# camera_connector.net
KiCad netlist of a schematic drawn in Altium Designer
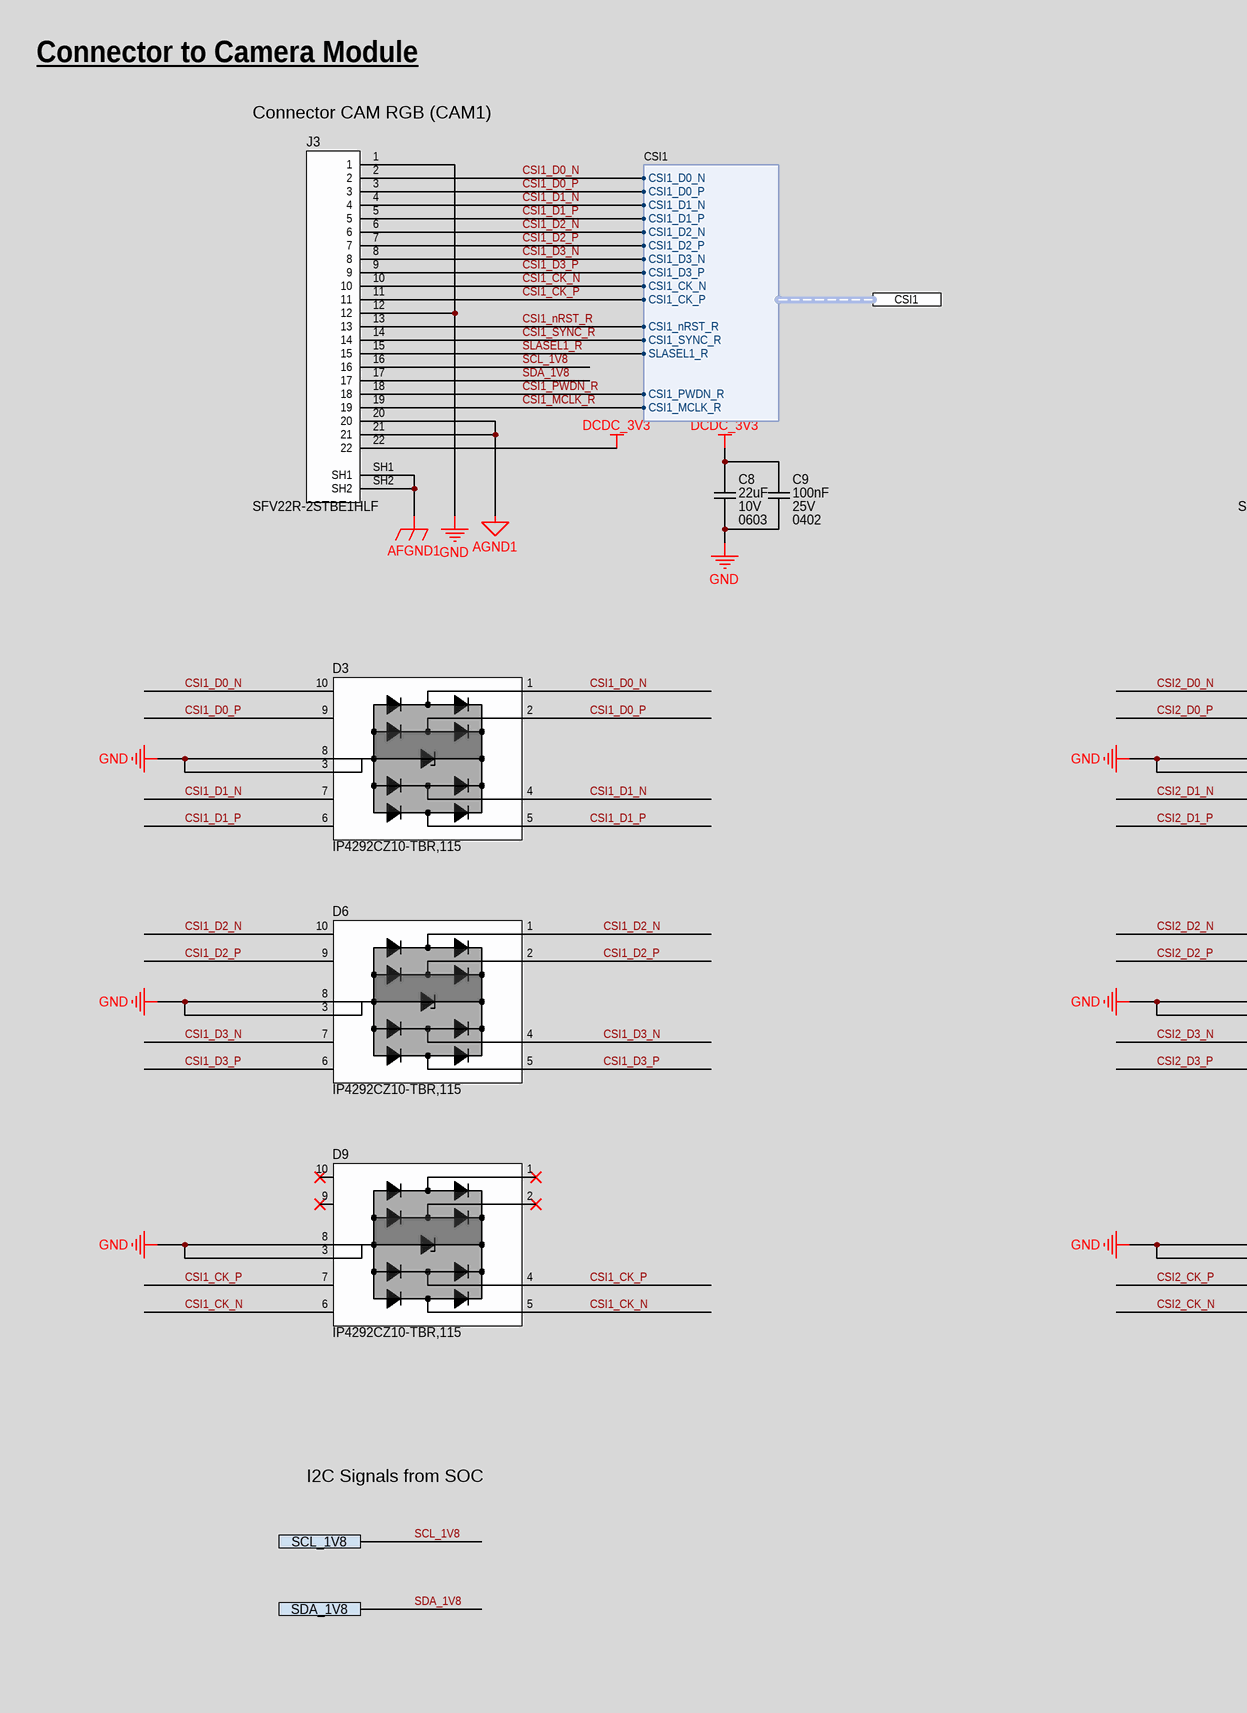
[diagram p0: camera_connector.SchDoc, left]
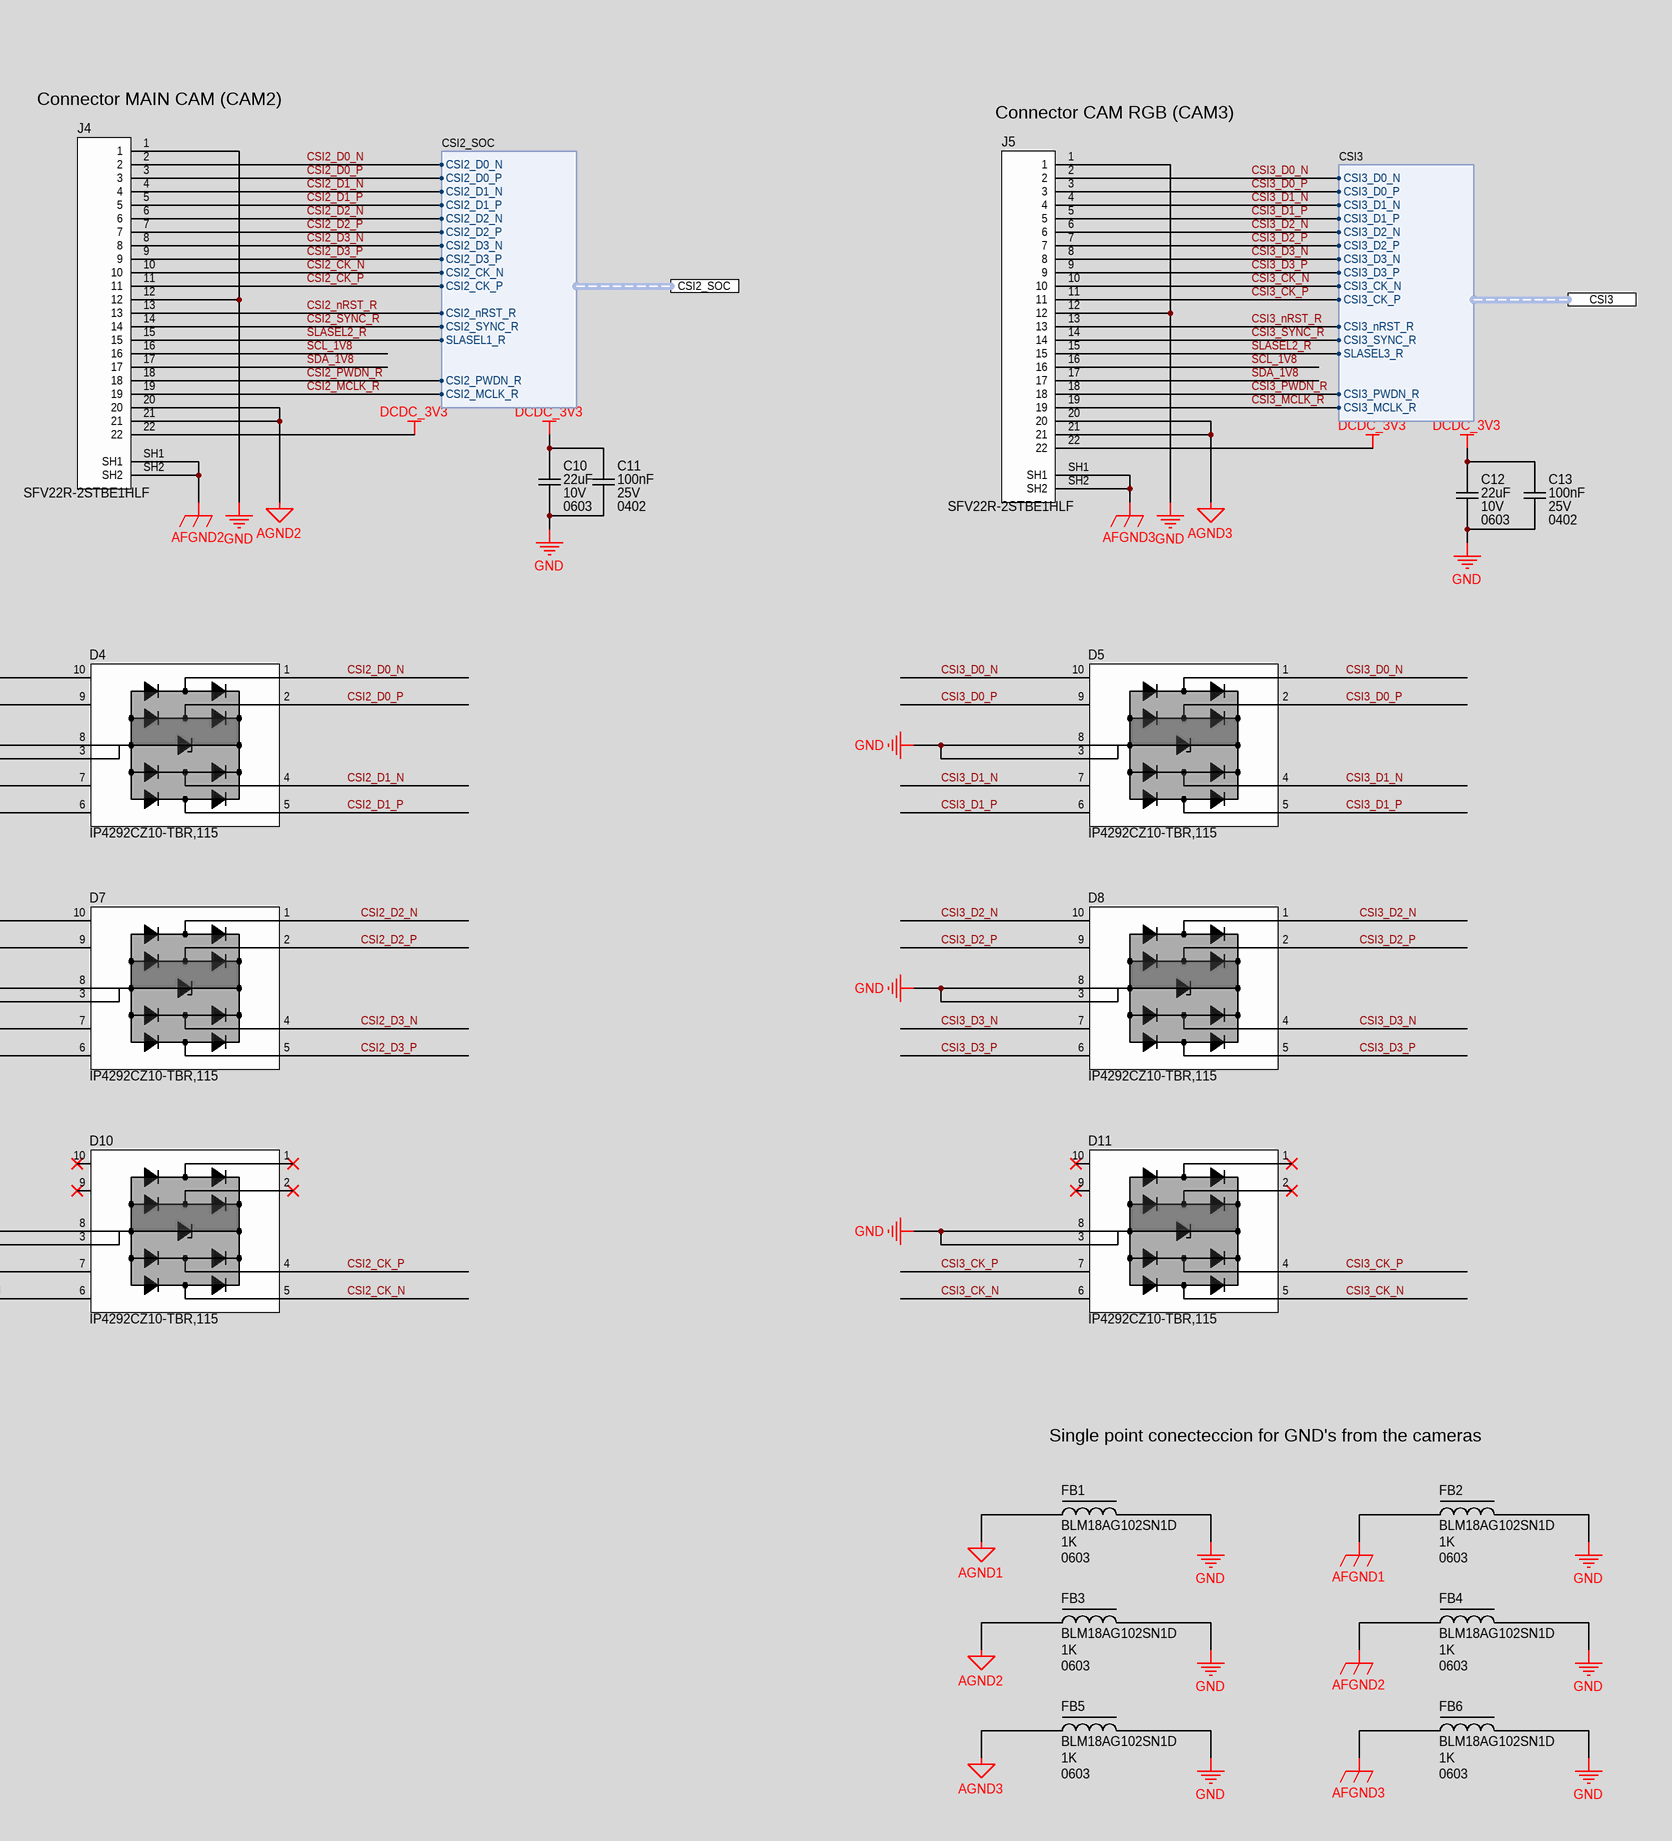
[diagram p1: camera_connector.SchDoc, right]

(export (version "E")
  (design (tool "Eeschema 10.0.6"))
  (components
    (comp (ref "C8")
      (value "C1608X5R1A226M080AC")
      (footprint "CAP_0603_CAPC1608X08N")
      (description "Multilayer Ceramic Capacitor, 22 uF, 10 V, ± 20%, X5R, 0603 [1608 Metric]")
      (fields
        (field (name "MANUFACTURER") "TDK")
        (field (name "TOLERANCE") "20%")
        (field (name "CAPACITANCE") "22uF")
        (field (name "VOLTAGE RATING") "10V")
        (field (name "CASE CODE (IMPERIAL)") "0603")
      )
      (libsource (lib "MGP Base_V1.0 RevA") (part "CAP_22UF_10V_X5R_0603"))
    )
    (comp (ref "C9")
      (value "CC0402KRX5R8BB104")
      (footprint "CAP_0402_CAPC1005X05N")
      (description "Multilayer Ceramic Capacitor, 0.1 uF, 25 V, ± 10%, X7R, 0402 [1005 Metric]")
      (fields
        (field (name "MANUFACTURER") "Yageo")
        (field (name "TOLERANCE") "10%")
        (field (name "CAPACITANCE") "100nF")
        (field (name "VOLTAGE RATING") "25V")
        (field (name "CASE/PACKAGE") "0402")
      )
      (libsource (lib "MGP Base_V1.0 RevA") (part "CAP_100NF_25V_X7R_0402"))
    )
    (comp (ref "C10")
      (value "C1608X5R1A226M080AC")
      (footprint "CAP_0603_CAPC1608X08N")
      (description "Multilayer Ceramic Capacitor, 22 uF, 10 V, ± 20%, X5R, 0603 [1608 Metric]")
      (fields
        (field (name "MANUFACTURER") "TDK")
        (field (name "TOLERANCE") "20%")
        (field (name "CAPACITANCE") "22uF")
        (field (name "VOLTAGE RATING") "10V")
        (field (name "CASE CODE (IMPERIAL)") "0603")
      )
      (libsource (lib "MGP Base_V1.0 RevA") (part "CAP_22UF_10V_X5R_0603"))
    )
    (comp (ref "C11")
      (value "CC0402KRX5R8BB104")
      (footprint "CAP_0402_CAPC1005X05N")
      (description "Multilayer Ceramic Capacitor, 0.1 uF, 25 V, ± 10%, X7R, 0402 [1005 Metric]")
      (fields
        (field (name "MANUFACTURER") "Yageo")
        (field (name "TOLERANCE") "10%")
        (field (name "CAPACITANCE") "100nF")
        (field (name "VOLTAGE RATING") "25V")
        (field (name "CASE/PACKAGE") "0402")
      )
      (libsource (lib "MGP Base_V1.0 RevA") (part "CAP_100NF_25V_X7R_0402"))
    )
    (comp (ref "C12")
      (value "C1608X5R1A226M080AC")
      (footprint "CAP_0603_CAPC1608X08N")
      (description "Multilayer Ceramic Capacitor, 22 uF, 10 V, ± 20%, X5R, 0603 [1608 Metric]")
      (fields
        (field (name "MANUFACTURER") "TDK")
        (field (name "TOLERANCE") "20%")
        (field (name "CAPACITANCE") "22uF")
        (field (name "VOLTAGE RATING") "10V")
        (field (name "CASE CODE (IMPERIAL)") "0603")
      )
      (libsource (lib "MGP Base_V1.0 RevA") (part "CAP_22UF_10V_X5R_0603"))
    )
    (comp (ref "C13")
      (value "CC0402KRX5R8BB104")
      (footprint "CAP_0402_CAPC1005X05N")
      (description "Multilayer Ceramic Capacitor, 0.1 uF, 25 V, ± 10%, X7R, 0402 [1005 Metric]")
      (fields
        (field (name "MANUFACTURER") "Yageo")
        (field (name "TOLERANCE") "10%")
        (field (name "CAPACITANCE") "100nF")
        (field (name "VOLTAGE RATING") "25V")
        (field (name "CASE/PACKAGE") "0402")
      )
      (libsource (lib "MGP Base_V1.0 RevA") (part "CAP_100NF_25V_X7R_0402"))
    )
    (comp (ref "D3")
      (value "IP4292CZ10-TBR,115")
      (footprint "DIO_TVS_SON50P100X250X50-10N")
      (description "IP4292CZ10 Series 4 Channel 4 V 0.55 pF ESD Protected TVS Diode - DFN2510A-10")
      (fields (field (name "MANUFACTURER") "Nexperia"))
      (libsource (lib "Electronic Devices_LIB") (part "DIO_TVS_4CH_4V_IP4292CZ10-TBR,115"))
    )
    (comp (ref "D4")
      (value "IP4292CZ10-TBR,115")
      (footprint "DIO_TVS_SON50P100X250X50-10N")
      (description "IP4292CZ10 Series 4 Channel 4 V 0.55 pF ESD Protected TVS Diode - DFN2510A-10")
      (fields (field (name "MANUFACTURER") "Nexperia"))
      (libsource (lib "Electronic Devices_LIB") (part "DIO_TVS_4CH_4V_IP4292CZ10-TBR,115"))
    )
    (comp (ref "D5")
      (value "IP4292CZ10-TBR,115")
      (footprint "DIO_TVS_SON50P100X250X50-10N")
      (description "IP4292CZ10 Series 4 Channel 4 V 0.55 pF ESD Protected TVS Diode - DFN2510A-10")
      (fields (field (name "MANUFACTURER") "Nexperia"))
      (libsource (lib "Electronic Devices_LIB") (part "DIO_TVS_4CH_4V_IP4292CZ10-TBR,115"))
    )
    (comp (ref "D6")
      (value "IP4292CZ10-TBR,115")
      (footprint "DIO_TVS_SON50P100X250X50-10N")
      (description "IP4292CZ10 Series 4 Channel 4 V 0.55 pF ESD Protected TVS Diode - DFN2510A-10")
      (fields (field (name "MANUFACTURER") "Nexperia"))
      (libsource (lib "Electronic Devices_LIB") (part "DIO_TVS_4CH_4V_IP4292CZ10-TBR,115"))
    )
    (comp (ref "D7")
      (value "IP4292CZ10-TBR,115")
      (footprint "DIO_TVS_SON50P100X250X50-10N")
      (description "IP4292CZ10 Series 4 Channel 4 V 0.55 pF ESD Protected TVS Diode - DFN2510A-10")
      (fields (field (name "MANUFACTURER") "Nexperia"))
      (libsource (lib "Electronic Devices_LIB") (part "DIO_TVS_4CH_4V_IP4292CZ10-TBR,115"))
    )
    (comp (ref "D8")
      (value "IP4292CZ10-TBR,115")
      (footprint "DIO_TVS_SON50P100X250X50-10N")
      (description "IP4292CZ10 Series 4 Channel 4 V 0.55 pF ESD Protected TVS Diode - DFN2510A-10")
      (fields (field (name "MANUFACTURER") "Nexperia"))
      (libsource (lib "Electronic Devices_LIB") (part "DIO_TVS_4CH_4V_IP4292CZ10-TBR,115"))
    )
    (comp (ref "D9")
      (value "IP4292CZ10-TBR,115")
      (footprint "DIO_TVS_SON50P100X250X50-10N")
      (description "IP4292CZ10 Series 4 Channel 4 V 0.55 pF ESD Protected TVS Diode - DFN2510A-10")
      (fields (field (name "MANUFACTURER") "Nexperia"))
      (libsource (lib "Electronic Devices_LIB") (part "DIO_TVS_4CH_4V_IP4292CZ10-TBR,115"))
    )
    (comp (ref "D10")
      (value "IP4292CZ10-TBR,115")
      (footprint "DIO_TVS_SON50P100X250X50-10N")
      (description "IP4292CZ10 Series 4 Channel 4 V 0.55 pF ESD Protected TVS Diode - DFN2510A-10")
      (fields (field (name "MANUFACTURER") "Nexperia"))
      (libsource (lib "Electronic Devices_LIB") (part "DIO_TVS_4CH_4V_IP4292CZ10-TBR,115"))
    )
    (comp (ref "D11")
      (value "IP4292CZ10-TBR,115")
      (footprint "DIO_TVS_SON50P100X250X50-10N")
      (description "IP4292CZ10 Series 4 Channel 4 V 0.55 pF ESD Protected TVS Diode - DFN2510A-10")
      (fields (field (name "MANUFACTURER") "Nexperia"))
      (libsource (lib "Electronic Devices_LIB") (part "DIO_TVS_4CH_4V_IP4292CZ10-TBR,115"))
    )
    (comp (ref "FB1")
      (value "BLM18AG102SN1D")
      (footprint "IND_0603_INDC1608X08N")
      (description "Ferrite Beads Multi-Layer 1KOhm 25% 100MHz 450mA 500mOhm DCR 0603 T/R")
      (fields
        (field (name "MANUFACTURER") "Murata")
        (field (name "TOLERANCE") "25%")
        (field (name "IMPEDANCE") "1K")
        (field (name "CASE/PACKAGE") "0603")
      )
      (libsource (lib "Electronic Devices_LIB") (part "IND_FERRITA_1K_450mA_BLM18AG102SN1D"))
    )
    (comp (ref "FB2")
      (value "BLM18AG102SN1D")
      (footprint "IND_0603_INDC1608X08N")
      (description "Ferrite Beads Multi-Layer 1KOhm 25% 100MHz 450mA 500mOhm DCR 0603 T/R")
      (fields
        (field (name "MANUFACTURER") "Murata")
        (field (name "TOLERANCE") "25%")
        (field (name "IMPEDANCE") "1K")
        (field (name "CASE/PACKAGE") "0603")
      )
      (libsource (lib "Electronic Devices_LIB") (part "IND_FERRITA_1K_450mA_BLM18AG102SN1D"))
    )
    (comp (ref "FB3")
      (value "BLM18AG102SN1D")
      (footprint "IND_0603_INDC1608X08N")
      (description "Ferrite Beads Multi-Layer 1KOhm 25% 100MHz 450mA 500mOhm DCR 0603 T/R")
      (fields
        (field (name "MANUFACTURER") "Murata")
        (field (name "TOLERANCE") "25%")
        (field (name "IMPEDANCE") "1K")
        (field (name "CASE/PACKAGE") "0603")
      )
      (libsource (lib "Electronic Devices_LIB") (part "IND_FERRITA_1K_450mA_BLM18AG102SN1D"))
    )
    (comp (ref "FB4")
      (value "BLM18AG102SN1D")
      (footprint "IND_0603_INDC1608X08N")
      (description "Ferrite Beads Multi-Layer 1KOhm 25% 100MHz 450mA 500mOhm DCR 0603 T/R")
      (fields
        (field (name "MANUFACTURER") "Murata")
        (field (name "TOLERANCE") "25%")
        (field (name "IMPEDANCE") "1K")
        (field (name "CASE/PACKAGE") "0603")
      )
      (libsource (lib "Electronic Devices_LIB") (part "IND_FERRITA_1K_450mA_BLM18AG102SN1D"))
    )
    (comp (ref "FB5")
      (value "BLM18AG102SN1D")
      (footprint "IND_0603_INDC1608X08N")
      (description "Ferrite Beads Multi-Layer 1KOhm 25% 100MHz 450mA 500mOhm DCR 0603 T/R")
      (fields
        (field (name "MANUFACTURER") "Murata")
        (field (name "TOLERANCE") "25%")
        (field (name "IMPEDANCE") "1K")
        (field (name "CASE/PACKAGE") "0603")
      )
      (libsource (lib "Electronic Devices_LIB") (part "IND_FERRITA_1K_450mA_BLM18AG102SN1D"))
    )
    (comp (ref "FB6")
      (value "BLM18AG102SN1D")
      (footprint "IND_0603_INDC1608X08N")
      (description "Ferrite Beads Multi-Layer 1KOhm 25% 100MHz 450mA 500mOhm DCR 0603 T/R")
      (fields
        (field (name "MANUFACTURER") "Murata")
        (field (name "TOLERANCE") "25%")
        (field (name "IMPEDANCE") "1K")
        (field (name "CASE/PACKAGE") "0603")
      )
      (libsource (lib "Electronic Devices_LIB") (part "IND_FERRITA_1K_450mA_BLM18AG102SN1D"))
    )
    (comp (ref "J3")
      (value "SFV22R-2STBE1HLF")
      (footprint "CONN_FPC_AMPHENOL_SFV22R-2STBE1HLF")
      (description "Conn FFC/FPC Connector SKT 22 POS 0.5mm Solder RA SMD Embossed T/R")
      (fields (field (name "MANUFACTURER") "Amphenol ICC / FCI"))
      (libsource (lib "Electronic Devices_LIB") (part "CONN_FPC_22P_0.5mm_SFV22R-2STBE1HLF"))
    )
    (comp (ref "J4")
      (value "SFV22R-2STBE1HLF")
      (footprint "CONN_FPC_AMPHENOL_SFV22R-2STBE1HLF")
      (description "Conn FFC/FPC Connector SKT 22 POS 0.5mm Solder RA SMD Embossed T/R")
      (fields (field (name "MANUFACTURER") "Amphenol ICC / FCI"))
      (libsource (lib "Electronic Devices_LIB") (part "CONN_FPC_22P_0.5mm_SFV22R-2STBE1HLF"))
    )
    (comp (ref "J5")
      (value "SFV22R-2STBE1HLF")
      (footprint "CONN_FPC_AMPHENOL_SFV22R-2STBE1HLF")
      (description "Conn FFC/FPC Connector SKT 22 POS 0.5mm Solder RA SMD Embossed T/R")
      (fields (field (name "MANUFACTURER") "Amphenol ICC / FCI"))
      (libsource (lib "Electronic Devices_LIB") (part "CONN_FPC_22P_0.5mm_SFV22R-2STBE1HLF"))
    )
  )
  (nets
    (net (code "4") (name "/CSI1_CK_N") (class "Default")
      (node (ref "D9") (pin "5") (pinfunction "CH4_5") (pintype "passive"))
      (node (ref "D9") (pin "6") (pinfunction "NC1_6") (pintype "passive"))
      (node (ref "J3") (pin "10") (pinfunction "10_10") (pintype "passive"))
    )
    (net (code "5") (name "/CSI1_CK_P") (class "Default")
      (node (ref "D9") (pin "4") (pinfunction "CH3_4") (pintype "passive"))
      (node (ref "D9") (pin "7") (pinfunction "NC2_7") (pintype "passive"))
      (node (ref "J3") (pin "11") (pinfunction "11_11") (pintype "passive"))
    )
    (net (code "6") (name "/CSI1_D0_N") (class "Default")
      (node (ref "D3") (pin "1") (pinfunction "CH1_1") (pintype "passive"))
      (node (ref "D3") (pin "10") (pinfunction "NC4_10") (pintype "passive"))
      (node (ref "J3") (pin "2") (pinfunction "2_2") (pintype "passive"))
    )
    (net (code "7") (name "/CSI1_D0_P") (class "Default")
      (node (ref "D3") (pin "2") (pinfunction "CH2_2") (pintype "passive"))
      (node (ref "D3") (pin "9") (pinfunction "NC3_9") (pintype "passive"))
      (node (ref "J3") (pin "3") (pinfunction "3_3") (pintype "passive"))
    )
    (net (code "8") (name "/CSI1_D1_N") (class "Default")
      (node (ref "D3") (pin "4") (pinfunction "CH3_4") (pintype "passive"))
      (node (ref "D3") (pin "7") (pinfunction "NC2_7") (pintype "passive"))
      (node (ref "J3") (pin "4") (pinfunction "4_4") (pintype "passive"))
    )
    (net (code "9") (name "/CSI1_D1_P") (class "Default")
      (node (ref "D3") (pin "5") (pinfunction "CH4_5") (pintype "passive"))
      (node (ref "D3") (pin "6") (pinfunction "NC1_6") (pintype "passive"))
      (node (ref "J3") (pin "5") (pinfunction "5_5") (pintype "passive"))
    )
    (net (code "10") (name "/CSI1_D2_N") (class "Default")
      (node (ref "D6") (pin "1") (pinfunction "CH1_1") (pintype "passive"))
      (node (ref "D6") (pin "10") (pinfunction "NC4_10") (pintype "passive"))
      (node (ref "J3") (pin "6") (pinfunction "6_6") (pintype "passive"))
    )
    (net (code "11") (name "/CSI1_D2_P") (class "Default")
      (node (ref "D6") (pin "2") (pinfunction "CH2_2") (pintype "passive"))
      (node (ref "D6") (pin "9") (pinfunction "NC3_9") (pintype "passive"))
      (node (ref "J3") (pin "7") (pinfunction "7_7") (pintype "passive"))
    )
    (net (code "12") (name "/CSI1_D3_N") (class "Default")
      (node (ref "D6") (pin "4") (pinfunction "CH3_4") (pintype "passive"))
      (node (ref "D6") (pin "7") (pinfunction "NC2_7") (pintype "passive"))
      (node (ref "J3") (pin "8") (pinfunction "8_8") (pintype "passive"))
    )
    (net (code "13") (name "/CSI1_D3_P") (class "Default")
      (node (ref "D6") (pin "5") (pinfunction "CH4_5") (pintype "passive"))
      (node (ref "D6") (pin "6") (pinfunction "NC1_6") (pintype "passive"))
      (node (ref "J3") (pin "9") (pinfunction "9_9") (pintype "passive"))
    )
    (net (code "14") (name "/CSI1_MCLK_R") (class "Default")
      (node (ref "J3") (pin "19") (pinfunction "19_19") (pintype "passive"))
    )
    (net (code "15") (name "/CSI1_PWDN_R") (class "Default")
      (node (ref "J3") (pin "18") (pinfunction "18_18") (pintype "passive"))
    )
    (net (code "16") (name "/CSI1_SYNC_R") (class "Default")
      (node (ref "J3") (pin "14") (pinfunction "14_14") (pintype "passive"))
    )
    (net (code "17") (name "/CSI1_nRST_R") (class "Default")
      (node (ref "J3") (pin "13") (pinfunction "13_13") (pintype "passive"))
    )
    (net (code "18") (name "/CSI2_CK_N") (class "Default")
      (node (ref "D10") (pin "5") (pinfunction "CH4_5") (pintype "passive"))
      (node (ref "D10") (pin "6") (pinfunction "NC1_6") (pintype "passive"))
      (node (ref "J4") (pin "10") (pinfunction "10_10") (pintype "passive"))
    )
    (net (code "19") (name "/CSI2_CK_P") (class "Default")
      (node (ref "D10") (pin "4") (pinfunction "CH3_4") (pintype "passive"))
      (node (ref "D10") (pin "7") (pinfunction "NC2_7") (pintype "passive"))
      (node (ref "J4") (pin "11") (pinfunction "11_11") (pintype "passive"))
    )
    (net (code "20") (name "/CSI2_D0_N") (class "Default")
      (node (ref "D4") (pin "1") (pinfunction "CH1_1") (pintype "passive"))
      (node (ref "D4") (pin "10") (pinfunction "NC4_10") (pintype "passive"))
      (node (ref "J4") (pin "2") (pinfunction "2_2") (pintype "passive"))
    )
    (net (code "21") (name "/CSI2_D0_P") (class "Default")
      (node (ref "D4") (pin "2") (pinfunction "CH2_2") (pintype "passive"))
      (node (ref "D4") (pin "9") (pinfunction "NC3_9") (pintype "passive"))
      (node (ref "J4") (pin "3") (pinfunction "3_3") (pintype "passive"))
    )
    (net (code "22") (name "/CSI2_D1_N") (class "Default")
      (node (ref "D4") (pin "4") (pinfunction "CH3_4") (pintype "passive"))
      (node (ref "D4") (pin "7") (pinfunction "NC2_7") (pintype "passive"))
      (node (ref "J4") (pin "4") (pinfunction "4_4") (pintype "passive"))
    )
    (net (code "23") (name "/CSI2_D1_P") (class "Default")
      (node (ref "D4") (pin "5") (pinfunction "CH4_5") (pintype "passive"))
      (node (ref "D4") (pin "6") (pinfunction "NC1_6") (pintype "passive"))
      (node (ref "J4") (pin "5") (pinfunction "5_5") (pintype "passive"))
    )
    (net (code "24") (name "/CSI2_D2_N") (class "Default")
      (node (ref "D7") (pin "1") (pinfunction "CH1_1") (pintype "passive"))
      (node (ref "D7") (pin "10") (pinfunction "NC4_10") (pintype "passive"))
      (node (ref "J4") (pin "6") (pinfunction "6_6") (pintype "passive"))
    )
    (net (code "25") (name "/CSI2_D2_P") (class "Default")
      (node (ref "D7") (pin "2") (pinfunction "CH2_2") (pintype "passive"))
      (node (ref "D7") (pin "9") (pinfunction "NC3_9") (pintype "passive"))
      (node (ref "J4") (pin "7") (pinfunction "7_7") (pintype "passive"))
    )
    (net (code "26") (name "/CSI2_D3_N") (class "Default")
      (node (ref "D7") (pin "4") (pinfunction "CH3_4") (pintype "passive"))
      (node (ref "D7") (pin "7") (pinfunction "NC2_7") (pintype "passive"))
      (node (ref "J4") (pin "8") (pinfunction "8_8") (pintype "passive"))
    )
    (net (code "27") (name "/CSI2_D3_P") (class "Default")
      (node (ref "D7") (pin "5") (pinfunction "CH4_5") (pintype "passive"))
      (node (ref "D7") (pin "6") (pinfunction "NC1_6") (pintype "passive"))
      (node (ref "J4") (pin "9") (pinfunction "9_9") (pintype "passive"))
    )
    (net (code "28") (name "/CSI2_MCLK_R") (class "Default")
      (node (ref "J4") (pin "19") (pinfunction "19_19") (pintype "passive"))
    )
    (net (code "29") (name "/CSI2_PWDN_R") (class "Default")
      (node (ref "J4") (pin "18") (pinfunction "18_18") (pintype "passive"))
    )
    (net (code "30") (name "/CSI2_SYNC_R") (class "Default")
      (node (ref "J4") (pin "14") (pinfunction "14_14") (pintype "passive"))
    )
    (net (code "31") (name "/CSI2_nRST_R") (class "Default")
      (node (ref "J4") (pin "13") (pinfunction "13_13") (pintype "passive"))
    )
    (net (code "32") (name "/CSI3_CK_N") (class "Default")
      (node (ref "D11") (pin "5") (pinfunction "CH4_5") (pintype "passive"))
      (node (ref "D11") (pin "6") (pinfunction "NC1_6") (pintype "passive"))
      (node (ref "J5") (pin "10") (pinfunction "10_10") (pintype "passive"))
    )
    (net (code "33") (name "/CSI3_CK_P") (class "Default")
      (node (ref "D11") (pin "4") (pinfunction "CH3_4") (pintype "passive"))
      (node (ref "D11") (pin "7") (pinfunction "NC2_7") (pintype "passive"))
      (node (ref "J5") (pin "11") (pinfunction "11_11") (pintype "passive"))
    )
    (net (code "34") (name "/CSI3_D0_N") (class "Default")
      (node (ref "D5") (pin "1") (pinfunction "CH1_1") (pintype "passive"))
      (node (ref "D5") (pin "10") (pinfunction "NC4_10") (pintype "passive"))
      (node (ref "J5") (pin "2") (pinfunction "2_2") (pintype "passive"))
    )
    (net (code "35") (name "/CSI3_D0_P") (class "Default")
      (node (ref "D5") (pin "2") (pinfunction "CH2_2") (pintype "passive"))
      (node (ref "D5") (pin "9") (pinfunction "NC3_9") (pintype "passive"))
      (node (ref "J5") (pin "3") (pinfunction "3_3") (pintype "passive"))
    )
    (net (code "36") (name "/CSI3_D1_N") (class "Default")
      (node (ref "D5") (pin "4") (pinfunction "CH3_4") (pintype "passive"))
      (node (ref "D5") (pin "7") (pinfunction "NC2_7") (pintype "passive"))
      (node (ref "J5") (pin "4") (pinfunction "4_4") (pintype "passive"))
    )
    (net (code "37") (name "/CSI3_D1_P") (class "Default")
      (node (ref "D5") (pin "5") (pinfunction "CH4_5") (pintype "passive"))
      (node (ref "D5") (pin "6") (pinfunction "NC1_6") (pintype "passive"))
      (node (ref "J5") (pin "5") (pinfunction "5_5") (pintype "passive"))
    )
    (net (code "38") (name "/CSI3_D2_N") (class "Default")
      (node (ref "D8") (pin "1") (pinfunction "CH1_1") (pintype "passive"))
      (node (ref "D8") (pin "10") (pinfunction "NC4_10") (pintype "passive"))
      (node (ref "J5") (pin "6") (pinfunction "6_6") (pintype "passive"))
    )
    (net (code "39") (name "/CSI3_D2_P") (class "Default")
      (node (ref "D8") (pin "2") (pinfunction "CH2_2") (pintype "passive"))
      (node (ref "D8") (pin "9") (pinfunction "NC3_9") (pintype "passive"))
      (node (ref "J5") (pin "7") (pinfunction "7_7") (pintype "passive"))
    )
    (net (code "40") (name "/CSI3_D3_N") (class "Default")
      (node (ref "D8") (pin "4") (pinfunction "CH3_4") (pintype "passive"))
      (node (ref "D8") (pin "7") (pinfunction "NC2_7") (pintype "passive"))
      (node (ref "J5") (pin "8") (pinfunction "8_8") (pintype "passive"))
    )
    (net (code "41") (name "/CSI3_D3_P") (class "Default")
      (node (ref "D8") (pin "5") (pinfunction "CH4_5") (pintype "passive"))
      (node (ref "D8") (pin "6") (pinfunction "NC1_6") (pintype "passive"))
      (node (ref "J5") (pin "9") (pinfunction "9_9") (pintype "passive"))
    )
    (net (code "42") (name "/CSI3_MCLK_R") (class "Default")
      (node (ref "J5") (pin "19") (pinfunction "19_19") (pintype "passive"))
    )
    (net (code "43") (name "/CSI3_PWDN_R") (class "Default")
      (node (ref "J5") (pin "18") (pinfunction "18_18") (pintype "passive"))
    )
    (net (code "44") (name "/CSI3_SYNC_R") (class "Default")
      (node (ref "J5") (pin "14") (pinfunction "14_14") (pintype "passive"))
    )
    (net (code "45") (name "/CSI3_nRST_R") (class "Default")
      (node (ref "J5") (pin "13") (pinfunction "13_13") (pintype "passive"))
    )
    (net (code "46") (name "/SCL_1V8") (class "Default")
      (node (ref "J3") (pin "16") (pinfunction "16_16") (pintype "passive"))
      (node (ref "J4") (pin "16") (pinfunction "16_16") (pintype "passive"))
      (node (ref "J5") (pin "16") (pinfunction "16_16") (pintype "passive"))
    )
    (net (code "47") (name "/SDA_1V8") (class "Default")
      (node (ref "J3") (pin "17") (pinfunction "17_17") (pintype "passive"))
      (node (ref "J4") (pin "17") (pinfunction "17_17") (pintype "passive"))
      (node (ref "J5") (pin "17") (pinfunction "17_17") (pintype "passive"))
    )
    (net (code "48") (name "/SLASEL1_R") (class "Default")
      (node (ref "J3") (pin "15") (pinfunction "15_15") (pintype "passive"))
    )
    (net (code "49") (name "/SLASEL2_R") (class "Default")
      (node (ref "J4") (pin "15") (pinfunction "15_15") (pintype "passive"))
      (node (ref "J5") (pin "15") (pinfunction "15_15") (pintype "passive"))
    )
    (net (code "53") (name "AFGND1") (class "Default")
      (node (ref "FB2") (pin "1") (pinfunction "1_1") (pintype "passive"))
      (node (ref "J3") (pin "SH1") (pinfunction "SH1_SH1") (pintype "passive"))
      (node (ref "J3") (pin "SH2") (pinfunction "SH2_SH2") (pintype "passive"))
    )
    (net (code "54") (name "AFGND2") (class "Default")
      (node (ref "FB4") (pin "1") (pinfunction "1_1") (pintype "passive"))
      (node (ref "J4") (pin "SH1") (pinfunction "SH1_SH1") (pintype "passive"))
      (node (ref "J4") (pin "SH2") (pinfunction "SH2_SH2") (pintype "passive"))
    )
    (net (code "55") (name "AFGND3") (class "Default")
      (node (ref "FB6") (pin "1") (pinfunction "1_1") (pintype "passive"))
      (node (ref "J5") (pin "SH1") (pinfunction "SH1_SH1") (pintype "passive"))
      (node (ref "J5") (pin "SH2") (pinfunction "SH2_SH2") (pintype "passive"))
    )
    (net (code "56") (name "AGND1") (class "Default")
      (node (ref "FB1") (pin "1") (pinfunction "1_1") (pintype "passive"))
      (node (ref "J3") (pin "20") (pinfunction "20_20") (pintype "passive"))
      (node (ref "J3") (pin "21") (pinfunction "21_21") (pintype "passive"))
    )
    (net (code "57") (name "AGND2") (class "Default")
      (node (ref "FB3") (pin "1") (pinfunction "1_1") (pintype "passive"))
      (node (ref "J4") (pin "20") (pinfunction "20_20") (pintype "passive"))
      (node (ref "J4") (pin "21") (pinfunction "21_21") (pintype "passive"))
    )
    (net (code "58") (name "AGND3") (class "Default")
      (node (ref "FB5") (pin "1") (pinfunction "1_1") (pintype "passive"))
      (node (ref "J5") (pin "20") (pinfunction "20_20") (pintype "passive"))
      (node (ref "J5") (pin "21") (pinfunction "21_21") (pintype "passive"))
    )
    (net (code "59") (name "DCDC_3V3") (class "Default")
      (node (ref "C10") (pin "2") (pinfunction "2_2") (pintype "passive"))
      (node (ref "C11") (pin "2") (pinfunction "2_2") (pintype "passive"))
      (node (ref "C12") (pin "2") (pinfunction "2_2") (pintype "passive"))
      (node (ref "C13") (pin "2") (pinfunction "2_2") (pintype "passive"))
      (node (ref "C8") (pin "2") (pinfunction "2_2") (pintype "passive"))
      (node (ref "C9") (pin "2") (pinfunction "2_2") (pintype "passive"))
      (node (ref "J3") (pin "22") (pinfunction "22_22") (pintype "passive"))
      (node (ref "J4") (pin "22") (pinfunction "22_22") (pintype "passive"))
      (node (ref "J5") (pin "22") (pinfunction "22_22") (pintype "passive"))
    )
    (net (code "60") (name "GND") (class "Default")
      (node (ref "C10") (pin "1") (pinfunction "1_1") (pintype "passive"))
      (node (ref "C11") (pin "1") (pinfunction "1_1") (pintype "passive"))
      (node (ref "C12") (pin "1") (pinfunction "1_1") (pintype "passive"))
      (node (ref "C13") (pin "1") (pinfunction "1_1") (pintype "passive"))
      (node (ref "C8") (pin "1") (pinfunction "1_1") (pintype "passive"))
      (node (ref "C9") (pin "1") (pinfunction "1_1") (pintype "passive"))
      (node (ref "D10") (pin "3") (pinfunction "GND1_3") (pintype "power_in"))
      (node (ref "D10") (pin "8") (pinfunction "GND2_8") (pintype "power_in"))
      (node (ref "D11") (pin "3") (pinfunction "GND1_3") (pintype "power_in"))
      (node (ref "D11") (pin "8") (pinfunction "GND2_8") (pintype "power_in"))
      (node (ref "D3") (pin "3") (pinfunction "GND1_3") (pintype "power_in"))
      (node (ref "D3") (pin "8") (pinfunction "GND2_8") (pintype "power_in"))
      (node (ref "D4") (pin "3") (pinfunction "GND1_3") (pintype "power_in"))
      (node (ref "D4") (pin "8") (pinfunction "GND2_8") (pintype "power_in"))
      (node (ref "D5") (pin "3") (pinfunction "GND1_3") (pintype "power_in"))
      (node (ref "D5") (pin "8") (pinfunction "GND2_8") (pintype "power_in"))
      (node (ref "D6") (pin "3") (pinfunction "GND1_3") (pintype "power_in"))
      (node (ref "D6") (pin "8") (pinfunction "GND2_8") (pintype "power_in"))
      (node (ref "D7") (pin "3") (pinfunction "GND1_3") (pintype "power_in"))
      (node (ref "D7") (pin "8") (pinfunction "GND2_8") (pintype "power_in"))
      (node (ref "D8") (pin "3") (pinfunction "GND1_3") (pintype "power_in"))
      (node (ref "D8") (pin "8") (pinfunction "GND2_8") (pintype "power_in"))
      (node (ref "D9") (pin "3") (pinfunction "GND1_3") (pintype "power_in"))
      (node (ref "D9") (pin "8") (pinfunction "GND2_8") (pintype "power_in"))
      (node (ref "FB1") (pin "2") (pinfunction "2_2") (pintype "passive"))
      (node (ref "FB2") (pin "2") (pinfunction "2_2") (pintype "passive"))
      (node (ref "FB3") (pin "2") (pinfunction "2_2") (pintype "passive"))
      (node (ref "FB4") (pin "2") (pinfunction "2_2") (pintype "passive"))
      (node (ref "FB5") (pin "2") (pinfunction "2_2") (pintype "passive"))
      (node (ref "FB6") (pin "2") (pinfunction "2_2") (pintype "passive"))
      (node (ref "J3") (pin "1") (pinfunction "1_1") (pintype "passive"))
      (node (ref "J3") (pin "12") (pinfunction "12_12") (pintype "passive"))
      (node (ref "J4") (pin "1") (pinfunction "1_1") (pintype "passive"))
      (node (ref "J4") (pin "12") (pinfunction "12_12") (pintype "passive"))
      (node (ref "J5") (pin "1") (pinfunction "1_1") (pintype "passive"))
      (node (ref "J5") (pin "12") (pinfunction "12_12") (pintype "passive"))
    )
    (net (code "61") (name "unconnected-(D9-CH1-Pad1)") (class "Default")
      (node (ref "D9") (pin "1") (pinfunction "CH1_1") (pintype "passive+no_connect"))
    )
    (net (code "62") (name "unconnected-(D9-CH2-Pad2)") (class "Default")
      (node (ref "D9") (pin "2") (pinfunction "CH2_2") (pintype "passive+no_connect"))
    )
    (net (code "63") (name "unconnected-(D9-NC3-Pad9)") (class "Default")
      (node (ref "D9") (pin "9") (pinfunction "NC3_9") (pintype "passive+no_connect"))
    )
    (net (code "64") (name "unconnected-(D9-NC4-Pad10)") (class "Default")
      (node (ref "D9") (pin "10") (pinfunction "NC4_10") (pintype "passive+no_connect"))
    )
    (net (code "65") (name "unconnected-(D10-CH1-Pad1)") (class "Default")
      (node (ref "D10") (pin "1") (pinfunction "CH1_1") (pintype "passive+no_connect"))
    )
    (net (code "66") (name "unconnected-(D10-CH2-Pad2)") (class "Default")
      (node (ref "D10") (pin "2") (pinfunction "CH2_2") (pintype "passive+no_connect"))
    )
    (net (code "67") (name "unconnected-(D10-NC3-Pad9)") (class "Default")
      (node (ref "D10") (pin "9") (pinfunction "NC3_9") (pintype "passive+no_connect"))
    )
    (net (code "68") (name "unconnected-(D10-NC4-Pad10)") (class "Default")
      (node (ref "D10") (pin "10") (pinfunction "NC4_10") (pintype "passive+no_connect"))
    )
    (net (code "69") (name "unconnected-(D11-CH1-Pad1)") (class "Default")
      (node (ref "D11") (pin "1") (pinfunction "CH1_1") (pintype "passive+no_connect"))
    )
    (net (code "70") (name "unconnected-(D11-CH2-Pad2)") (class "Default")
      (node (ref "D11") (pin "2") (pinfunction "CH2_2") (pintype "passive+no_connect"))
    )
    (net (code "71") (name "unconnected-(D11-NC3-Pad9)") (class "Default")
      (node (ref "D11") (pin "9") (pinfunction "NC3_9") (pintype "passive+no_connect"))
    )
    (net (code "72") (name "unconnected-(D11-NC4-Pad10)") (class "Default")
      (node (ref "D11") (pin "10") (pinfunction "NC4_10") (pintype "passive+no_connect"))
    )
  )
)
